# 2_waffling60-NMB_matrix.net
KiCad netlist of a schematic drawn in Altium Designer
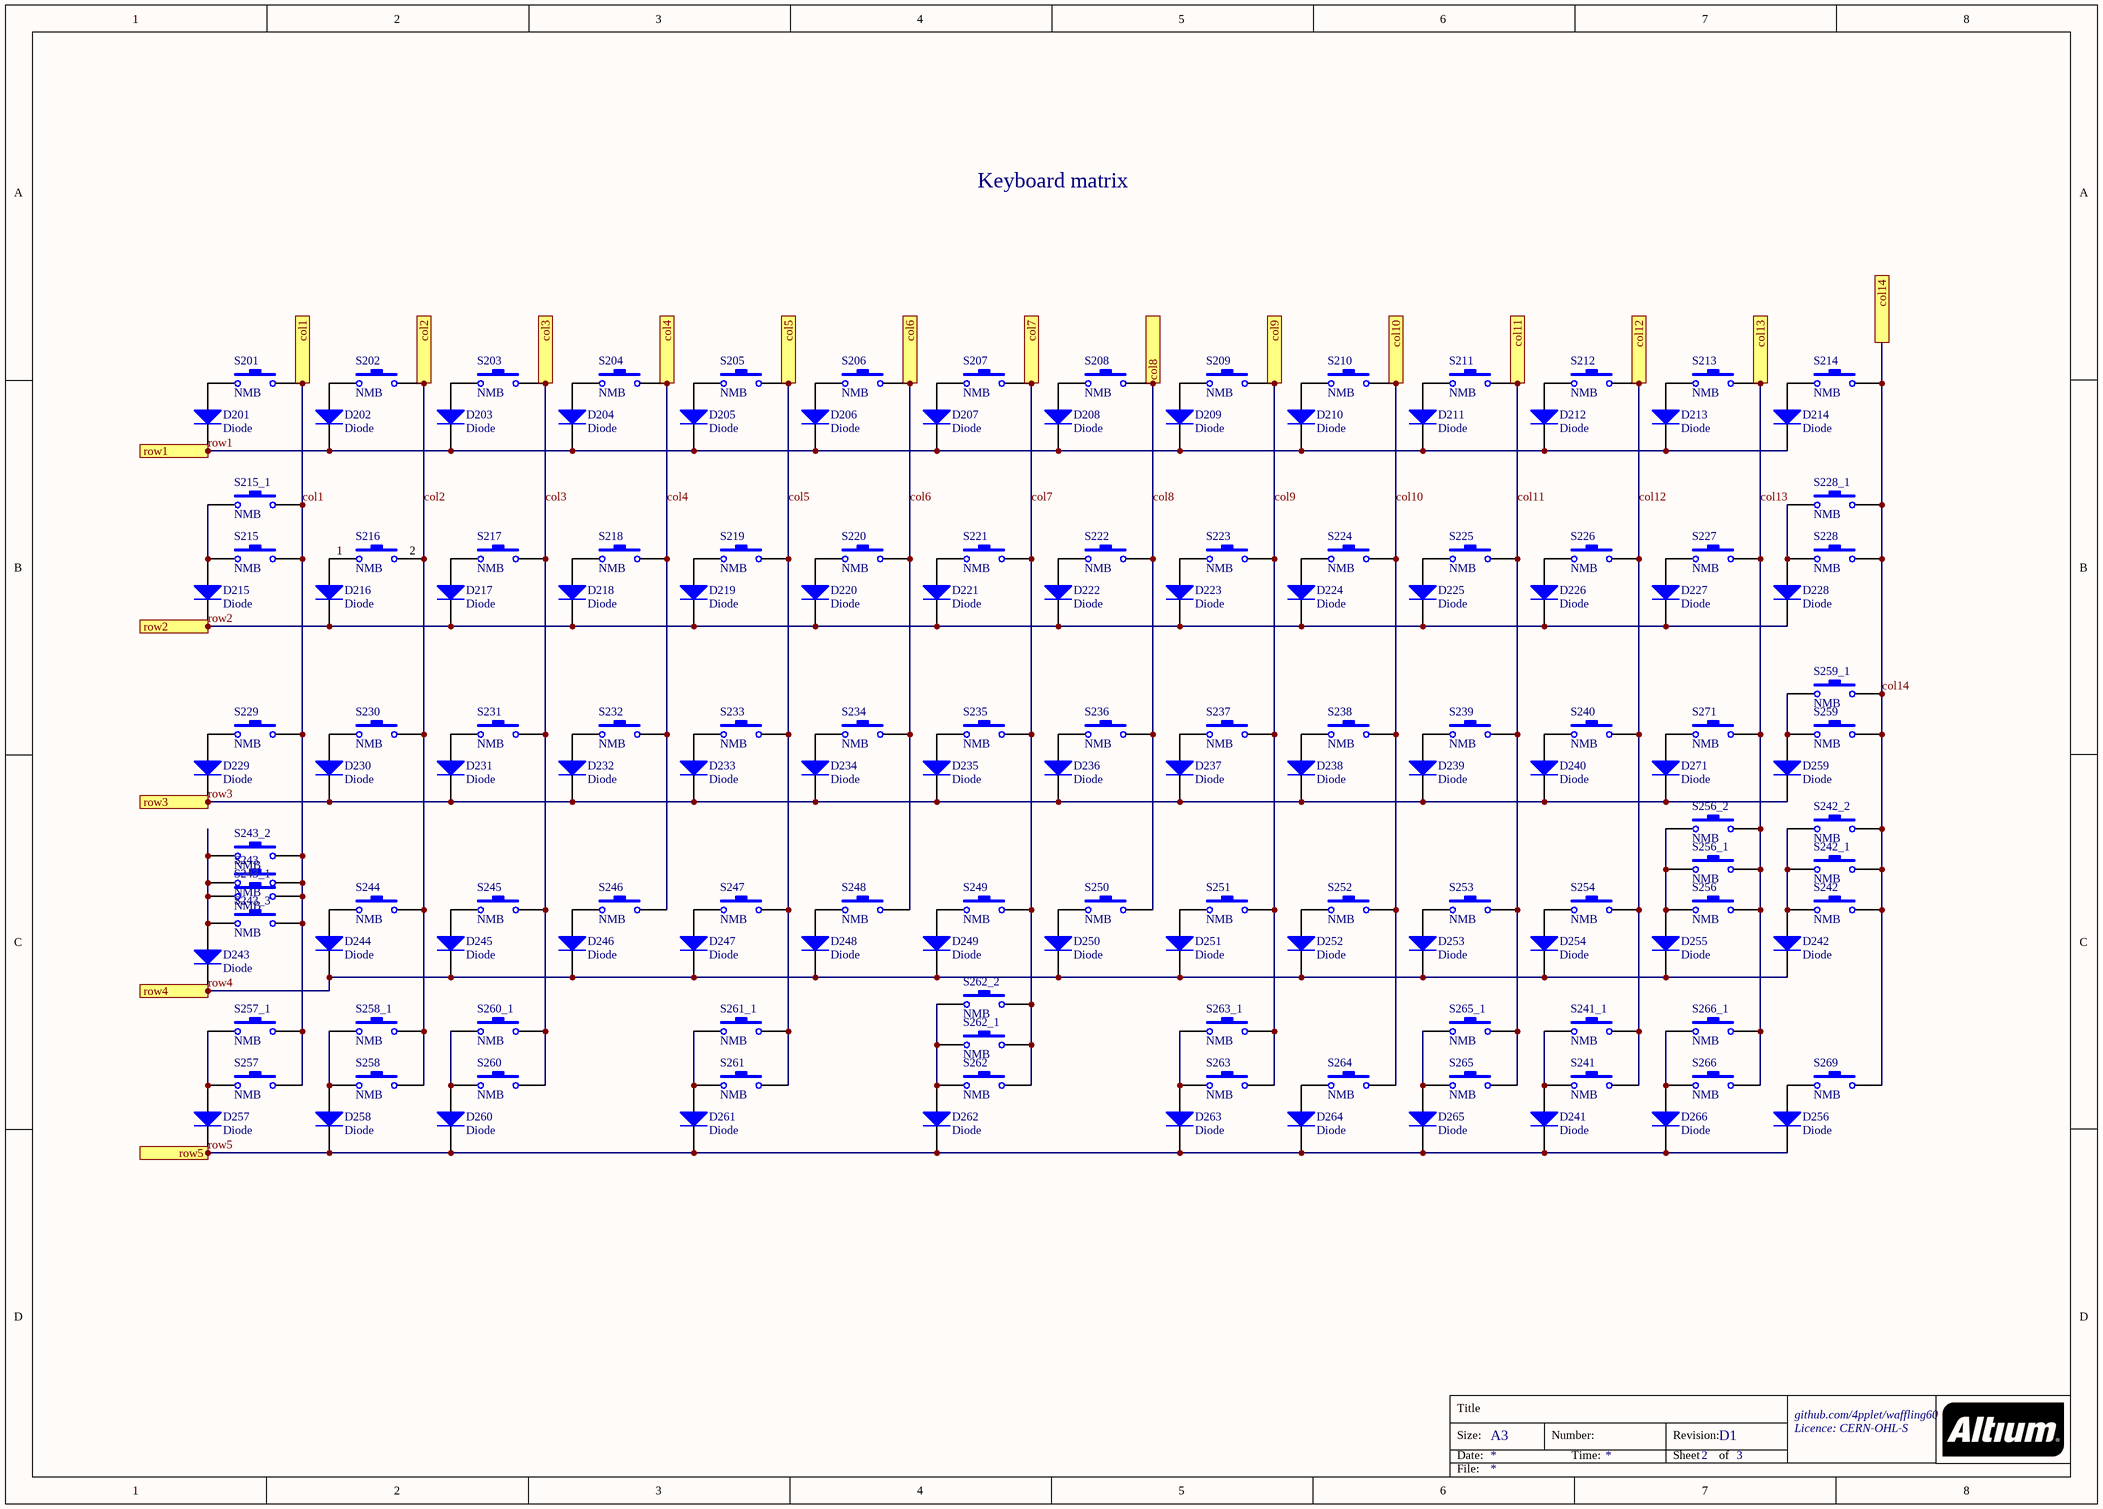
[diagram p0: 2_waffling60-NMB_matrix.SchDoc]

(export (version "E")
  (design (tool "Eeschema 10.0.6"))
  (components
    (comp (ref "D201")
      (value "Diode")
      (footprint "SOD-123")
      (description "Default Diode")
      (fields (field (name "LCSC PART #") "C81598") (field (name "MRF.PART") "1N4148W"))
      (libsource (lib "Miscellaneous Devices") (part "Diode"))
    )
    (comp (ref "D202")
      (value "Diode")
      (footprint "SOD-123")
      (description "Default Diode")
      (fields (field (name "LCSC PART #") "C81598") (field (name "MRF.PART") "1N4148W"))
      (libsource (lib "Miscellaneous Devices") (part "Diode"))
    )
    (comp (ref "D203")
      (value "Diode")
      (footprint "SOD-123")
      (description "Default Diode")
      (fields (field (name "LCSC PART #") "C81598") (field (name "MRF.PART") "1N4148W"))
      (libsource (lib "Miscellaneous Devices") (part "Diode"))
    )
    (comp (ref "D204")
      (value "Diode")
      (footprint "SOD-123")
      (description "Default Diode")
      (fields (field (name "LCSC PART #") "C81598") (field (name "MRF.PART") "1N4148W"))
      (libsource (lib "Miscellaneous Devices") (part "Diode"))
    )
    (comp (ref "D205")
      (value "Diode")
      (footprint "SOD-123")
      (description "Default Diode")
      (fields (field (name "LCSC PART #") "C81598") (field (name "MRF.PART") "1N4148W"))
      (libsource (lib "Miscellaneous Devices") (part "Diode"))
    )
    (comp (ref "D206")
      (value "Diode")
      (footprint "SOD-123")
      (description "Default Diode")
      (fields (field (name "LCSC PART #") "C81598") (field (name "MRF.PART") "1N4148W"))
      (libsource (lib "Miscellaneous Devices") (part "Diode"))
    )
    (comp (ref "D207")
      (value "Diode")
      (footprint "SOD-123")
      (description "Default Diode")
      (fields (field (name "LCSC PART #") "C81598") (field (name "MRF.PART") "1N4148W"))
      (libsource (lib "Miscellaneous Devices") (part "Diode"))
    )
    (comp (ref "D208")
      (value "Diode")
      (footprint "SOD-123")
      (description "Default Diode")
      (fields (field (name "LCSC PART #") "C81598") (field (name "MRF.PART") "1N4148W"))
      (libsource (lib "Miscellaneous Devices") (part "Diode"))
    )
    (comp (ref "D209")
      (value "Diode")
      (footprint "SOD-123")
      (description "Default Diode")
      (fields (field (name "LCSC PART #") "C81598") (field (name "MRF.PART") "1N4148W"))
      (libsource (lib "Miscellaneous Devices") (part "Diode"))
    )
    (comp (ref "D210")
      (value "Diode")
      (footprint "SOD-123")
      (description "Default Diode")
      (fields (field (name "LCSC PART #") "C81598") (field (name "MRF.PART") "1N4148W"))
      (libsource (lib "Miscellaneous Devices") (part "Diode"))
    )
    (comp (ref "D211")
      (value "Diode")
      (footprint "SOD-123")
      (description "Default Diode")
      (fields (field (name "LCSC PART #") "C81598") (field (name "MRF.PART") "1N4148W"))
      (libsource (lib "Miscellaneous Devices") (part "Diode"))
    )
    (comp (ref "D212")
      (value "Diode")
      (footprint "SOD-123")
      (description "Default Diode")
      (fields (field (name "LCSC PART #") "C81598") (field (name "MRF.PART") "1N4148W"))
      (libsource (lib "Miscellaneous Devices") (part "Diode"))
    )
    (comp (ref "D213")
      (value "Diode")
      (footprint "SOD-123")
      (description "Default Diode")
      (fields (field (name "LCSC PART #") "C81598") (field (name "MRF.PART") "1N4148W"))
      (libsource (lib "Miscellaneous Devices") (part "Diode"))
    )
    (comp (ref "D214")
      (value "Diode")
      (footprint "SOD-123")
      (description "Default Diode")
      (fields (field (name "LCSC PART #") "C81598") (field (name "MRF.PART") "1N4148W"))
      (libsource (lib "Miscellaneous Devices") (part "Diode"))
    )
    (comp (ref "D215")
      (value "Diode")
      (footprint "SOD-123")
      (description "Default Diode")
      (fields (field (name "LCSC PART #") "C81598") (field (name "MRF.PART") "1N4148W"))
      (libsource (lib "Miscellaneous Devices") (part "Diode"))
    )
    (comp (ref "D216")
      (value "Diode")
      (footprint "SOD-123")
      (description "Default Diode")
      (fields (field (name "LCSC PART #") "C81598") (field (name "MRF.PART") "1N4148W"))
      (libsource (lib "Miscellaneous Devices") (part "Diode"))
    )
    (comp (ref "D217")
      (value "Diode")
      (footprint "SOD-123")
      (description "Default Diode")
      (fields (field (name "LCSC PART #") "C81598") (field (name "MRF.PART") "1N4148W"))
      (libsource (lib "Miscellaneous Devices") (part "Diode"))
    )
    (comp (ref "D218")
      (value "Diode")
      (footprint "SOD-123")
      (description "Default Diode")
      (fields (field (name "LCSC PART #") "C81598") (field (name "MRF.PART") "1N4148W"))
      (libsource (lib "Miscellaneous Devices") (part "Diode"))
    )
    (comp (ref "D219")
      (value "Diode")
      (footprint "SOD-123")
      (description "Default Diode")
      (fields (field (name "LCSC PART #") "C81598") (field (name "MRF.PART") "1N4148W"))
      (libsource (lib "Miscellaneous Devices") (part "Diode"))
    )
    (comp (ref "D220")
      (value "Diode")
      (footprint "SOD-123")
      (description "Default Diode")
      (fields (field (name "LCSC PART #") "C81598") (field (name "MRF.PART") "1N4148W"))
      (libsource (lib "Miscellaneous Devices") (part "Diode"))
    )
    (comp (ref "D221")
      (value "Diode")
      (footprint "SOD-123")
      (description "Default Diode")
      (fields (field (name "LCSC PART #") "C81598") (field (name "MRF.PART") "1N4148W"))
      (libsource (lib "Miscellaneous Devices") (part "Diode"))
    )
    (comp (ref "D222")
      (value "Diode")
      (footprint "SOD-123")
      (description "Default Diode")
      (fields (field (name "LCSC PART #") "C81598") (field (name "MRF.PART") "1N4148W"))
      (libsource (lib "Miscellaneous Devices") (part "Diode"))
    )
    (comp (ref "D223")
      (value "Diode")
      (footprint "SOD-123")
      (description "Default Diode")
      (fields (field (name "LCSC PART #") "C81598") (field (name "MRF.PART") "1N4148W"))
      (libsource (lib "Miscellaneous Devices") (part "Diode"))
    )
    (comp (ref "D224")
      (value "Diode")
      (footprint "SOD-123")
      (description "Default Diode")
      (fields (field (name "LCSC PART #") "C81598") (field (name "MRF.PART") "1N4148W"))
      (libsource (lib "Miscellaneous Devices") (part "Diode"))
    )
    (comp (ref "D225")
      (value "Diode")
      (footprint "SOD-123")
      (description "Default Diode")
      (fields (field (name "LCSC PART #") "C81598") (field (name "MRF.PART") "1N4148W"))
      (libsource (lib "Miscellaneous Devices") (part "Diode"))
    )
    (comp (ref "D226")
      (value "Diode")
      (footprint "SOD-123")
      (description "Default Diode")
      (fields (field (name "LCSC PART #") "C81598") (field (name "MRF.PART") "1N4148W"))
      (libsource (lib "Miscellaneous Devices") (part "Diode"))
    )
    (comp (ref "D227")
      (value "Diode")
      (footprint "SOD-123")
      (description "Default Diode")
      (fields (field (name "LCSC PART #") "C81598") (field (name "MRF.PART") "1N4148W"))
      (libsource (lib "Miscellaneous Devices") (part "Diode"))
    )
    (comp (ref "D228")
      (value "Diode")
      (footprint "SOD-123")
      (description "Default Diode")
      (fields (field (name "LCSC PART #") "C81598") (field (name "MRF.PART") "1N4148W"))
      (libsource (lib "Miscellaneous Devices") (part "Diode"))
    )
    (comp (ref "D229")
      (value "Diode")
      (footprint "SOD-123")
      (description "Default Diode")
      (fields (field (name "LCSC PART #") "C81598") (field (name "MRF.PART") "1N4148W"))
      (libsource (lib "Miscellaneous Devices") (part "Diode"))
    )
    (comp (ref "D230")
      (value "Diode")
      (footprint "SOD-123")
      (description "Default Diode")
      (fields (field (name "LCSC PART #") "C81598") (field (name "MRF.PART") "1N4148W"))
      (libsource (lib "Miscellaneous Devices") (part "Diode"))
    )
    (comp (ref "D231")
      (value "Diode")
      (footprint "SOD-123")
      (description "Default Diode")
      (fields (field (name "LCSC PART #") "C81598") (field (name "MRF.PART") "1N4148W"))
      (libsource (lib "Miscellaneous Devices") (part "Diode"))
    )
    (comp (ref "D232")
      (value "Diode")
      (footprint "SOD-123")
      (description "Default Diode")
      (fields (field (name "LCSC PART #") "C81598") (field (name "MRF.PART") "1N4148W"))
      (libsource (lib "Miscellaneous Devices") (part "Diode"))
    )
    (comp (ref "D233")
      (value "Diode")
      (footprint "SOD-123")
      (description "Default Diode")
      (fields (field (name "LCSC PART #") "C81598") (field (name "MRF.PART") "1N4148W"))
      (libsource (lib "Miscellaneous Devices") (part "Diode"))
    )
    (comp (ref "D234")
      (value "Diode")
      (footprint "SOD-123")
      (description "Default Diode")
      (fields (field (name "LCSC PART #") "C81598") (field (name "MRF.PART") "1N4148W"))
      (libsource (lib "Miscellaneous Devices") (part "Diode"))
    )
    (comp (ref "D235")
      (value "Diode")
      (footprint "SOD-123")
      (description "Default Diode")
      (fields (field (name "LCSC PART #") "C81598") (field (name "MRF.PART") "1N4148W"))
      (libsource (lib "Miscellaneous Devices") (part "Diode"))
    )
    (comp (ref "D236")
      (value "Diode")
      (footprint "SOD-123")
      (description "Default Diode")
      (fields (field (name "LCSC PART #") "C81598") (field (name "MRF.PART") "1N4148W"))
      (libsource (lib "Miscellaneous Devices") (part "Diode"))
    )
    (comp (ref "D237")
      (value "Diode")
      (footprint "SOD-123")
      (description "Default Diode")
      (fields (field (name "LCSC PART #") "C81598") (field (name "MRF.PART") "1N4148W"))
      (libsource (lib "Miscellaneous Devices") (part "Diode"))
    )
    (comp (ref "D238")
      (value "Diode")
      (footprint "SOD-123")
      (description "Default Diode")
      (fields (field (name "LCSC PART #") "C81598") (field (name "MRF.PART") "1N4148W"))
      (libsource (lib "Miscellaneous Devices") (part "Diode"))
    )
    (comp (ref "D239")
      (value "Diode")
      (footprint "SOD-123")
      (description "Default Diode")
      (fields (field (name "LCSC PART #") "C81598") (field (name "MRF.PART") "1N4148W"))
      (libsource (lib "Miscellaneous Devices") (part "Diode"))
    )
    (comp (ref "D240")
      (value "Diode")
      (footprint "SOD-123")
      (description "Default Diode")
      (fields (field (name "LCSC PART #") "C81598") (field (name "MRF.PART") "1N4148W"))
      (libsource (lib "Miscellaneous Devices") (part "Diode"))
    )
    (comp (ref "D241")
      (value "Diode")
      (footprint "SOD-123")
      (description "Default Diode")
      (fields (field (name "LCSC PART #") "C81598") (field (name "MRF.PART") "1N4148W"))
      (libsource (lib "Miscellaneous Devices") (part "Diode"))
    )
    (comp (ref "D242")
      (value "Diode")
      (footprint "SOD-123")
      (description "Default Diode")
      (fields (field (name "LCSC PART #") "C81598") (field (name "MRF.PART") "1N4148W"))
      (libsource (lib "Miscellaneous Devices") (part "Diode"))
    )
    (comp (ref "D243")
      (value "Diode")
      (footprint "SOD-123")
      (description "Default Diode")
      (fields (field (name "LCSC PART #") "C81598") (field (name "MRF.PART") "1N4148W"))
      (libsource (lib "Miscellaneous Devices") (part "Diode"))
    )
    (comp (ref "D244")
      (value "Diode")
      (footprint "SOD-123")
      (description "Default Diode")
      (fields (field (name "LCSC PART #") "C81598") (field (name "MRF.PART") "1N4148W"))
      (libsource (lib "Miscellaneous Devices") (part "Diode"))
    )
    (comp (ref "D245")
      (value "Diode")
      (footprint "SOD-123")
      (description "Default Diode")
      (fields (field (name "LCSC PART #") "C81598") (field (name "MRF.PART") "1N4148W"))
      (libsource (lib "Miscellaneous Devices") (part "Diode"))
    )
    (comp (ref "D246")
      (value "Diode")
      (footprint "SOD-123")
      (description "Default Diode")
      (fields (field (name "LCSC PART #") "C81598") (field (name "MRF.PART") "1N4148W"))
      (libsource (lib "Miscellaneous Devices") (part "Diode"))
    )
    (comp (ref "D247")
      (value "Diode")
      (footprint "SOD-123")
      (description "Default Diode")
      (fields (field (name "LCSC PART #") "C81598") (field (name "MRF.PART") "1N4148W"))
      (libsource (lib "Miscellaneous Devices") (part "Diode"))
    )
    (comp (ref "D248")
      (value "Diode")
      (footprint "SOD-123")
      (description "Default Diode")
      (fields (field (name "LCSC PART #") "C81598") (field (name "MRF.PART") "1N4148W"))
      (libsource (lib "Miscellaneous Devices") (part "Diode"))
    )
    (comp (ref "D249")
      (value "Diode")
      (footprint "SOD-123")
      (description "Default Diode")
      (fields (field (name "LCSC PART #") "C81598") (field (name "MRF.PART") "1N4148W"))
      (libsource (lib "Miscellaneous Devices") (part "Diode"))
    )
    (comp (ref "D250")
      (value "Diode")
      (footprint "SOD-123")
      (description "Default Diode")
      (fields (field (name "LCSC PART #") "C81598") (field (name "MRF.PART") "1N4148W"))
      (libsource (lib "Miscellaneous Devices") (part "Diode"))
    )
    (comp (ref "D251")
      (value "Diode")
      (footprint "SOD-123")
      (description "Default Diode")
      (fields (field (name "LCSC PART #") "C81598") (field (name "MRF.PART") "1N4148W"))
      (libsource (lib "Miscellaneous Devices") (part "Diode"))
    )
    (comp (ref "D252")
      (value "Diode")
      (footprint "SOD-123")
      (description "Default Diode")
      (fields (field (name "LCSC PART #") "C81598") (field (name "MRF.PART") "1N4148W"))
      (libsource (lib "Miscellaneous Devices") (part "Diode"))
    )
    (comp (ref "D253")
      (value "Diode")
      (footprint "SOD-123")
      (description "Default Diode")
      (fields (field (name "LCSC PART #") "C81598") (field (name "MRF.PART") "1N4148W"))
      (libsource (lib "Miscellaneous Devices") (part "Diode"))
    )
    (comp (ref "D254")
      (value "Diode")
      (footprint "SOD-123")
      (description "Default Diode")
      (fields (field (name "LCSC PART #") "C81598") (field (name "MRF.PART") "1N4148W"))
      (libsource (lib "Miscellaneous Devices") (part "Diode"))
    )
    (comp (ref "D255")
      (value "Diode")
      (footprint "SOD-123")
      (description "Default Diode")
      (fields (field (name "LCSC PART #") "C81598") (field (name "MRF.PART") "1N4148W"))
      (libsource (lib "Miscellaneous Devices") (part "Diode"))
    )
    (comp (ref "D256")
      (value "Diode")
      (footprint "SOD-123")
      (description "Default Diode")
      (fields (field (name "LCSC PART #") "C81598") (field (name "MRF.PART") "1N4148W"))
      (libsource (lib "Miscellaneous Devices") (part "Diode"))
    )
    (comp (ref "D257")
      (value "Diode")
      (footprint "SOD-123")
      (description "Default Diode")
      (fields (field (name "LCSC PART #") "C81598") (field (name "MRF.PART") "1N4148W"))
      (libsource (lib "Miscellaneous Devices") (part "Diode"))
    )
    (comp (ref "D258")
      (value "Diode")
      (footprint "SOD-123")
      (description "Default Diode")
      (fields (field (name "LCSC PART #") "C81598") (field (name "MRF.PART") "1N4148W"))
      (libsource (lib "Miscellaneous Devices") (part "Diode"))
    )
    (comp (ref "D259")
      (value "Diode")
      (footprint "SOD-123")
      (description "Default Diode")
      (fields (field (name "LCSC PART #") "C81598") (field (name "MRF.PART") "1N4148W"))
      (libsource (lib "Miscellaneous Devices") (part "Diode"))
    )
    (comp (ref "D260")
      (value "Diode")
      (footprint "SOD-123")
      (description "Default Diode")
      (fields (field (name "LCSC PART #") "C81598") (field (name "MRF.PART") "1N4148W"))
      (libsource (lib "Miscellaneous Devices") (part "Diode"))
    )
    (comp (ref "D261")
      (value "Diode")
      (footprint "SOD-123")
      (description "Default Diode")
      (fields (field (name "LCSC PART #") "C81598") (field (name "MRF.PART") "1N4148W"))
      (libsource (lib "Miscellaneous Devices") (part "Diode"))
    )
    (comp (ref "D262")
      (value "Diode")
      (footprint "SOD-123")
      (description "Default Diode")
      (fields (field (name "LCSC PART #") "C81598") (field (name "MRF.PART") "1N4148W"))
      (libsource (lib "Miscellaneous Devices") (part "Diode"))
    )
    (comp (ref "D263")
      (value "Diode")
      (footprint "SOD-123")
      (description "Default Diode")
      (fields (field (name "LCSC PART #") "C81598") (field (name "MRF.PART") "1N4148W"))
      (libsource (lib "Miscellaneous Devices") (part "Diode"))
    )
    (comp (ref "D264")
      (value "Diode")
      (footprint "SOD-123")
      (description "Default Diode")
      (fields (field (name "LCSC PART #") "C81598") (field (name "MRF.PART") "1N4148W"))
      (libsource (lib "Miscellaneous Devices") (part "Diode"))
    )
    (comp (ref "D265")
      (value "Diode")
      (footprint "SOD-123")
      (description "Default Diode")
      (fields (field (name "LCSC PART #") "C81598") (field (name "MRF.PART") "1N4148W"))
      (libsource (lib "Miscellaneous Devices") (part "Diode"))
    )
    (comp (ref "D266")
      (value "Diode")
      (footprint "SOD-123")
      (description "Default Diode")
      (fields (field (name "LCSC PART #") "C81598") (field (name "MRF.PART") "1N4148W"))
      (libsource (lib "Miscellaneous Devices") (part "Diode"))
    )
    (comp (ref "D271")
      (value "Diode")
      (footprint "SOD-123")
      (description "Default Diode")
      (fields (field (name "LCSC PART #") "C81598") (field (name "MRF.PART") "1N4148W"))
      (libsource (lib "Miscellaneous Devices") (part "Diode"))
    )
    (comp (ref "S201")
      (value "NMB")
      (footprint "NMB-Switch 1U - switched pol  - no allignment pins")
      (description "Switch")
      (libsource (lib "Miscellaneous Devices") (part "SW-PB"))
    )
    (comp (ref "S202")
      (value "NMB")
      (footprint "NMB-Switch 1U - no allignment pins")
      (description "Switch")
      (libsource (lib "Miscellaneous Devices") (part "SW-PB"))
    )
    (comp (ref "S203")
      (value "NMB")
      (footprint "NMB-Switch 1U - switched pol  - no allignment pins")
      (description "Switch")
      (libsource (lib "Miscellaneous Devices") (part "SW-PB"))
    )
    (comp (ref "S204")
      (value "NMB")
      (footprint "NMB-Switch 1U - switched pol  - no allignment pins")
      (description "Switch")
      (libsource (lib "Miscellaneous Devices") (part "SW-PB"))
    )
    (comp (ref "S205")
      (value "NMB")
      (footprint "NMB-Switch 1U - switched pol  - no allignment pins")
      (description "Switch")
      (libsource (lib "Miscellaneous Devices") (part "SW-PB"))
    )
    (comp (ref "S206")
      (value "NMB")
      (footprint "NMB-Switch 1U - switched pol  - no allignment pins")
      (description "Switch")
      (libsource (lib "Miscellaneous Devices") (part "SW-PB"))
    )
    (comp (ref "S207")
      (value "NMB")
      (footprint "NMB-Switch 1U - switched pol  - no allignment pins")
      (description "Switch")
      (libsource (lib "Miscellaneous Devices") (part "SW-PB"))
    )
    (comp (ref "S208")
      (value "NMB")
      (footprint "NMB-Switch 1U - switched pol  - no allignment pins")
      (description "Switch")
      (libsource (lib "Miscellaneous Devices") (part "SW-PB"))
    )
    (comp (ref "S209")
      (value "NMB")
      (footprint "NMB-Switch 1U - switched pol  - no allignment pins")
      (description "Switch")
      (libsource (lib "Miscellaneous Devices") (part "SW-PB"))
    )
    (comp (ref "S210")
      (value "NMB")
      (footprint "NMB-Switch 1U - switched pol  - no allignment pins")
      (description "Switch")
      (libsource (lib "Miscellaneous Devices") (part "SW-PB"))
    )
    (comp (ref "S211")
      (value "NMB")
      (footprint "NMB-Switch 1U - switched pol  - no allignment pins")
      (description "Switch")
      (libsource (lib "Miscellaneous Devices") (part "SW-PB"))
    )
    (comp (ref "S212")
      (value "NMB")
      (footprint "NMB-Switch 1U - switched pol  - no allignment pins")
      (description "Switch")
      (libsource (lib "Miscellaneous Devices") (part "SW-PB"))
    )
    (comp (ref "S213")
      (value "NMB")
      (footprint "NMB-Switch 1U - switched pol  - no allignment pins")
      (description "Switch")
      (libsource (lib "Miscellaneous Devices") (part "SW-PB"))
    )
    (comp (ref "S214")
      (value "NMB")
      (footprint "NMB-Switch 1U - no allignment pins")
      (description "Switch")
      (libsource (lib "Miscellaneous Devices") (part "SW-PB"))
    )
    (comp (ref "S215")
      (value "NMB")
      (footprint "NMB-Switch 1U - no allignment pins")
      (description "TAB")
      (libsource (lib "Miscellaneous Devices") (part "SW-PB"))
    )
    (comp (ref "S215_1")
      (value "NMB")
      (footprint "NMB-Switch 1U - no allignment pins")
      (description "TAB")
      (libsource (lib "Miscellaneous Devices") (part "SW-PB"))
    )
    (comp (ref "S216")
      (value "NMB")
      (footprint "NMB-Switch 1U - switched pol  - no allignment pins")
      (description "Switch")
      (libsource (lib "") (part "SW-PB_2"))
    )
    (comp (ref "S217")
      (value "NMB")
      (footprint "NMB-Switch 1U - switched pol  - no allignment pins")
      (description "Switch")
      (libsource (lib "Miscellaneous Devices") (part "SW-PB"))
    )
    (comp (ref "S218")
      (value "NMB")
      (footprint "NMB-Switch 1U - switched pol  - no allignment pins")
      (description "Switch")
      (libsource (lib "Miscellaneous Devices") (part "SW-PB"))
    )
    (comp (ref "S219")
      (value "NMB")
      (footprint "NMB-Switch 1U - switched pol  - no allignment pins")
      (description "Switch")
      (libsource (lib "Miscellaneous Devices") (part "SW-PB"))
    )
    (comp (ref "S220")
      (value "NMB")
      (footprint "NMB-Switch 1U - no allignment pins")
      (description "Switch")
      (libsource (lib "Miscellaneous Devices") (part "SW-PB"))
    )
    (comp (ref "S221")
      (value "NMB")
      (footprint "NMB-Switch 1U - switched pol  - no allignment pins")
      (description "Switch")
      (libsource (lib "Miscellaneous Devices") (part "SW-PB"))
    )
    (comp (ref "S222")
      (value "NMB")
      (footprint "NMB-Switch 1U - no allignment pins")
      (description "Switch")
      (libsource (lib "Miscellaneous Devices") (part "SW-PB"))
    )
    (comp (ref "S223")
      (value "NMB")
      (footprint "NMB-Switch 1U - switched pol  - no allignment pins")
      (description "Switch")
      (libsource (lib "Miscellaneous Devices") (part "SW-PB"))
    )
    (comp (ref "S224")
      (value "NMB")
      (footprint "NMB-Switch 1U - switched pol  - no allignment pins")
      (description "Switch")
      (libsource (lib "Miscellaneous Devices") (part "SW-PB"))
    )
    (comp (ref "S225")
      (value "NMB")
      (footprint "NMB-Switch 1U - switched pol  - no allignment pins")
      (description "Switch")
      (libsource (lib "Miscellaneous Devices") (part "SW-PB"))
    )
    (comp (ref "S226")
      (value "NMB")
      (footprint "NMB-Switch 1U - no allignment pins")
      (description "Switch")
      (libsource (lib "Miscellaneous Devices") (part "SW-PB"))
    )
    (comp (ref "S227")
      (value "NMB")
      (footprint "NMB-Switch 1U - no allignment pins")
      (description "Switch")
      (libsource (lib "Miscellaneous Devices") (part "SW-PB"))
    )
    (comp (ref "S228")
      (value "NMB")
      (footprint "NMB-Switch 1U - no allignment pins")
      (description "Switch")
      (libsource (lib "Miscellaneous Devices") (part "SW-PB"))
    )
    (comp (ref "S228_1")
      (value "NMB")
      (footprint "NMB-Switch 1U - no allignment pins")
      (description "Switch")
      (libsource (lib "Miscellaneous Devices") (part "SW-PB"))
    )
    (comp (ref "S229")
      (value "NMB")
      (footprint "NMB-Switch 1U - no allignment pins")
      (description "Switch")
      (libsource (lib "Miscellaneous Devices") (part "SW-PB"))
    )
    (comp (ref "S230")
      (value "NMB")
      (footprint "NMB-Switch 1U - no allignment pins")
      (description "Switch")
      (libsource (lib "Miscellaneous Devices") (part "SW-PB"))
    )
    (comp (ref "S231")
      (value "NMB")
      (footprint "NMB-Switch 1U - switched pol  - no allignment pins")
      (description "Switch")
      (libsource (lib "Miscellaneous Devices") (part "SW-PB"))
    )
    (comp (ref "S232")
      (value "NMB")
      (footprint "NMB-Switch 1U - switched pol  - no allignment pins")
      (description "Switch")
      (libsource (lib "Miscellaneous Devices") (part "SW-PB"))
    )
    (comp (ref "S233")
      (value "NMB")
      (footprint "NMB-Switch 1U - switched pol  - no allignment pins")
      (description "Switch")
      (libsource (lib "Miscellaneous Devices") (part "SW-PB"))
    )
    (comp (ref "S234")
      (value "NMB")
      (footprint "NMB-Switch 1U - no allignment pins")
      (description "Switch")
      (libsource (lib "Miscellaneous Devices") (part "SW-PB"))
    )
    (comp (ref "S235")
      (value "NMB")
      (footprint "NMB-Switch 1U - switched pol  - no allignment pins")
      (description "Switch")
      (libsource (lib "Miscellaneous Devices") (part "SW-PB"))
    )
    (comp (ref "S236")
      (value "NMB")
      (footprint "NMB-Switch 1U - switched pol  - no allignment pins")
      (description "Switch")
      (libsource (lib "Miscellaneous Devices") (part "SW-PB"))
    )
    (comp (ref "S237")
      (value "NMB")
      (footprint "NMB-Switch 1U - switched pol  - no allignment pins")
      (description "Switch")
      (libsource (lib "Miscellaneous Devices") (part "SW-PB"))
    )
    (comp (ref "S238")
      (value "NMB")
      (footprint "NMB-Switch 1U - switched pol  - no allignment pins")
      (description "Switch")
      (libsource (lib "Miscellaneous Devices") (part "SW-PB"))
    )
    (comp (ref "S239")
      (value "NMB")
      (footprint "NMB-Switch 1U - switched pol  - no allignment pins")
      (description "Switch")
      (libsource (lib "Miscellaneous Devices") (part "SW-PB"))
    )
    (comp (ref "S240")
      (value "NMB")
      (footprint "NMB-Switch 1U - switched pol  - no allignment pins")
      (description "Switch")
      (libsource (lib "Miscellaneous Devices") (part "SW-PB"))
    )
    (comp (ref "S241")
      (value "NMB")
      (footprint "NMB-Switch 1U - no allignment pins")
      (description "Switch")
      (libsource (lib "Miscellaneous Devices") (part "SW-PB"))
    )
    (comp (ref "S241_1")
      (value "NMB")
      (footprint "NMB-Switch 1U - no allignment pins")
      (description "Switch")
      (libsource (lib "Miscellaneous Devices") (part "SW-PB"))
    )
    (comp (ref "S242")
      (value "NMB")
      (footprint "NMB-Switch 1U - switched pol  - no allignment pins")
      (description "Switch")
      (libsource (lib "Miscellaneous Devices") (part "SW-PB"))
    )
    (comp (ref "S242_1")
      (value "NMB")
      (footprint "NMB-Switch 1U - no allignment pins")
      (description "Switch")
      (libsource (lib "Miscellaneous Devices") (part "SW-PB"))
    )
    (comp (ref "S242_2")
      (value "NMB")
      (footprint "NMB-Switch 1U - switched pol  - no allignment pins")
      (description "Switch")
      (libsource (lib "Miscellaneous Devices") (part "SW-PB"))
    )
    (comp (ref "S243")
      (value "NMB")
      (footprint "NMB-Switch 1U - switched pol  - no allignment pins")
      (description "Switch")
      (libsource (lib "Miscellaneous Devices") (part "SW-PB"))
    )
    (comp (ref "S243_1")
      (value "NMB")
      (footprint "NMB-Switch 1U - switched pol  - no allignment pins")
      (description "Switch")
      (libsource (lib "Miscellaneous Devices") (part "SW-PB"))
    )
    (comp (ref "S243_2")
      (value "NMB")
      (footprint "NMB-Switch 1U - no allignment pins")
      (description "Switch")
      (libsource (lib "Miscellaneous Devices") (part "SW-PB"))
    )
    (comp (ref "S243_3")
      (value "NMB")
      (footprint "NMB-Switch 1U - no allignment pins")
      (description "Switch")
      (libsource (lib "Miscellaneous Devices") (part "SW-PB"))
    )
    (comp (ref "S244")
      (value "NMB")
      (footprint "NMB-Switch 1U - no allignment pins")
      (description "Switch")
      (libsource (lib "Miscellaneous Devices") (part "SW-PB"))
    )
    (comp (ref "S245")
      (value "NMB")
      (footprint "NMB-Switch 1U - switched pol  - no allignment pins")
      (description "Switch")
      (libsource (lib "Miscellaneous Devices") (part "SW-PB"))
    )
    (comp (ref "S246")
      (value "NMB")
      (footprint "NMB-Switch 1U - switched pol  - no allignment pins")
      (description "Switch")
      (libsource (lib "Miscellaneous Devices") (part "SW-PB"))
    )
    (comp (ref "S247")
      (value "NMB")
      (footprint "NMB-Switch 1U - switched pol  - no allignment pins")
      (description "Switch")
      (libsource (lib "Miscellaneous Devices") (part "SW-PB"))
    )
    (comp (ref "S248")
      (value "NMB")
      (footprint "NMB-Switch 1U - switched pol  - no allignment pins")
      (description "Switch")
      (libsource (lib "Miscellaneous Devices") (part "SW-PB"))
    )
    (comp (ref "S249")
      (value "NMB")
      (footprint "NMB-Switch 1U - switched pol  - no allignment pins")
      (description "Switch")
      (libsource (lib "Miscellaneous Devices") (part "SW-PB"))
    )
    (comp (ref "S250")
      (value "NMB")
      (footprint "NMB-Switch 1U - switched pol  - no allignment pins")
      (description "Switch")
      (libsource (lib "Miscellaneous Devices") (part "SW-PB"))
    )
    (comp (ref "S251")
      (value "NMB")
      (footprint "NMB-Switch 1U - switched pol  - no allignment pins")
      (description "Switch")
      (libsource (lib "Miscellaneous Devices") (part "SW-PB"))
    )
    (comp (ref "S252")
      (value "NMB")
      (footprint "NMB-Switch 1U - switched pol  - no allignment pins")
      (description "Switch")
      (libsource (lib "Miscellaneous Devices") (part "SW-PB"))
    )
    (comp (ref "S253")
      (value "NMB")
      (footprint "NMB-Switch 1U - switched pol  - no allignment pins")
      (description "Switch")
      (libsource (lib "Miscellaneous Devices") (part "SW-PB"))
    )
    (comp (ref "S254")
      (value "NMB")
      (footprint "NMB-Switch 1U - switched pol  - no allignment pins")
      (description "Switch")
      (libsource (lib "Miscellaneous Devices") (part "SW-PB"))
    )
    (comp (ref "S256")
      (value "NMB")
      (footprint "NMB-Switch 1U - switched pol  - no allignment pins")
      (description "Switch")
      (libsource (lib "Miscellaneous Devices") (part "SW-PB"))
    )
    (comp (ref "S256_1")
      (value "NMB")
      (footprint "NMB-Switch 1U - switched pol  - no allignment pins")
      (description "Switch")
      (libsource (lib "Miscellaneous Devices") (part "SW-PB"))
    )
    (comp (ref "S256_2")
      (value "NMB")
      (footprint "NMB-Switch 1U - no allignment pins")
      (description "Switch")
      (libsource (lib "Miscellaneous Devices") (part "SW-PB"))
    )
    (comp (ref "S257")
      (value "NMB")
      (footprint "NMB-Switch 1U - no allignment pins")
      (description "Switch")
      (libsource (lib "Miscellaneous Devices") (part "SW-PB"))
    )
    (comp (ref "S257_1")
      (value "NMB")
      (footprint "NMB-Switch 1U - no allignment pins")
      (description "Switch")
      (libsource (lib "Miscellaneous Devices") (part "SW-PB"))
    )
    (comp (ref "S258")
      (value "NMB")
      (footprint "NMB-Switch 1U - no allignment pins")
      (description "Switch")
      (libsource (lib "Miscellaneous Devices") (part "SW-PB"))
    )
    (comp (ref "S258_1")
      (value "NMB")
      (footprint "NMB-Switch 1U - switched pol  - no allignment pins")
      (description "Switch")
      (libsource (lib "Miscellaneous Devices") (part "SW-PB"))
    )
    (comp (ref "S259")
      (value "NMB")
      (footprint "NMB-Switch 1U - no allignment pins")
      (description "Switch")
      (libsource (lib "") (part "SW-PB_1"))
    )
    (comp (ref "S259_1")
      (value "NMB")
      (footprint "NMB-Switch 1U - no allignment pins")
      (description "Switch")
      (libsource (lib "Miscellaneous Devices") (part "SW-PB"))
    )
    (comp (ref "S260")
      (value "NMB")
      (footprint "NMB-Switch 1U - no allignment pins")
      (description "Switch")
      (libsource (lib "Miscellaneous Devices") (part "SW-PB"))
    )
    (comp (ref "S260_1")
      (value "NMB")
      (footprint "NMB-Switch 1U - switched pol  - no allignment pins")
      (description "Switch")
      (libsource (lib "Miscellaneous Devices") (part "SW-PB"))
    )
    (comp (ref "S261")
      (value "NMB")
      (footprint "NMB-Switch 1U - no allignment pins")
      (description "Switch")
      (libsource (lib "Miscellaneous Devices") (part "SW-PB"))
    )
    (comp (ref "S261_1")
      (value "NMB")
      (footprint "NMB-Switch 1U - no allignment pins")
      (description "Switch")
      (libsource (lib "Miscellaneous Devices") (part "SW-PB"))
    )
    (comp (ref "S262")
      (value "NMB")
      (footprint "NMB-Switch 1U - no allignment pins")
      (description "Switch")
      (libsource (lib "Miscellaneous Devices") (part "SW-PB"))
    )
    (comp (ref "S262_1")
      (value "NMB")
      (footprint "NMB-Switch 1U - no allignment pins")
      (description "Switch")
      (libsource (lib "Miscellaneous Devices") (part "SW-PB"))
    )
    (comp (ref "S262_2")
      (value "NMB")
      (footprint "NMB-Switch 1U - switched pol  - no allignment pins")
      (description "Switch")
      (libsource (lib "Miscellaneous Devices") (part "SW-PB"))
    )
    (comp (ref "S263")
      (value "NMB")
      (footprint "NMB-Switch 1U - no allignment pins")
      (description "Switch")
      (libsource (lib "Miscellaneous Devices") (part "SW-PB"))
    )
    (comp (ref "S263_1")
      (value "NMB")
      (footprint "NMB-Switch 1U - switched pol  - no allignment pins")
      (description "Switch")
      (libsource (lib "Miscellaneous Devices") (part "SW-PB"))
    )
    (comp (ref "S264")
      (value "NMB")
      (footprint "NMB-Switch 1U - switched pol  - no allignment pins")
      (description "Switch")
      (libsource (lib "Miscellaneous Devices") (part "SW-PB"))
    )
    (comp (ref "S265")
      (value "NMB")
      (footprint "NMB-Switch 1U - no allignment pins")
      (description "Switch")
      (libsource (lib "Miscellaneous Devices") (part "SW-PB"))
    )
    (comp (ref "S265_1")
      (value "NMB")
      (footprint "NMB-Switch 1U - no allignment pins")
      (description "Switch")
      (libsource (lib "Miscellaneous Devices") (part "SW-PB"))
    )
    (comp (ref "S266")
      (value "NMB")
      (footprint "NMB-Switch 1U - no allignment pins")
      (description "Switch")
      (libsource (lib "Miscellaneous Devices") (part "SW-PB"))
    )
    (comp (ref "S266_1")
      (value "NMB")
      (footprint "NMB-Switch 1U - no allignment pins")
      (description "Switch")
      (libsource (lib "Miscellaneous Devices") (part "SW-PB"))
    )
    (comp (ref "S269")
      (value "NMB")
      (footprint "NMB-Switch 1U - no allignment pins")
      (description "Switch")
      (libsource (lib "Miscellaneous Devices") (part "SW-PB"))
    )
    (comp (ref "S271")
      (value "NMB")
      (footprint "NMB-Switch 1U - no allignment pins")
      (description "Switch")
      (libsource (lib "Miscellaneous Devices") (part "SW-PB"))
    )
  )
  (nets
    (net (code "1") (name "/col1") (class "Default")
      (node (ref "S201") (pin "2") (pinfunction "2_2") (pintype "passive"))
      (node (ref "S215") (pin "2") (pinfunction "2_2") (pintype "passive"))
      (node (ref "S215_1") (pin "2") (pinfunction "2_2") (pintype "passive"))
      (node (ref "S229") (pin "1") (pinfunction "1_1") (pintype "passive"))
      (node (ref "S243") (pin "2") (pinfunction "2_2") (pintype "passive"))
      (node (ref "S243_1") (pin "2") (pinfunction "2_2") (pintype "passive"))
      (node (ref "S243_2") (pin "2") (pinfunction "2_2") (pintype "passive"))
      (node (ref "S243_3") (pin "2") (pinfunction "2_2") (pintype "passive"))
      (node (ref "S257") (pin "1") (pinfunction "1_1") (pintype "passive"))
      (node (ref "S257_1") (pin "1") (pinfunction "1_1") (pintype "passive"))
    )
    (net (code "2") (name "/col2") (class "Default")
      (node (ref "S202") (pin "2") (pinfunction "2_2") (pintype "passive"))
      (node (ref "S216") (pin "2") (pinfunction "2_2") (pintype "passive"))
      (node (ref "S230") (pin "2") (pinfunction "2_2") (pintype "passive"))
      (node (ref "S244") (pin "1") (pinfunction "1_1") (pintype "passive"))
      (node (ref "S258") (pin "2") (pinfunction "2_2") (pintype "passive"))
      (node (ref "S258_1") (pin "1") (pinfunction "1_1") (pintype "passive"))
    )
    (net (code "3") (name "/col3") (class "Default")
      (node (ref "S203") (pin "2") (pinfunction "2_2") (pintype "passive"))
      (node (ref "S217") (pin "2") (pinfunction "2_2") (pintype "passive"))
      (node (ref "S231") (pin "2") (pinfunction "2_2") (pintype "passive"))
      (node (ref "S245") (pin "2") (pinfunction "2_2") (pintype "passive"))
      (node (ref "S260") (pin "2") (pinfunction "2_2") (pintype "passive"))
      (node (ref "S260_1") (pin "1") (pinfunction "1_1") (pintype "passive"))
    )
    (net (code "4") (name "/col4") (class "Default")
      (node (ref "S204") (pin "2") (pinfunction "2_2") (pintype "passive"))
      (node (ref "S218") (pin "2") (pinfunction "2_2") (pintype "passive"))
      (node (ref "S232") (pin "2") (pinfunction "2_2") (pintype "passive"))
      (node (ref "S246") (pin "2") (pinfunction "2_2") (pintype "passive"))
    )
    (net (code "5") (name "/col5") (class "Default")
      (node (ref "S205") (pin "2") (pinfunction "2_2") (pintype "passive"))
      (node (ref "S219") (pin "2") (pinfunction "2_2") (pintype "passive"))
      (node (ref "S233") (pin "2") (pinfunction "2_2") (pintype "passive"))
      (node (ref "S247") (pin "2") (pinfunction "2_2") (pintype "passive"))
      (node (ref "S261") (pin "2") (pinfunction "2_2") (pintype "passive"))
      (node (ref "S261_1") (pin "2") (pinfunction "2_2") (pintype "passive"))
    )
    (net (code "6") (name "/col6") (class "Default")
      (node (ref "S206") (pin "2") (pinfunction "2_2") (pintype "passive"))
      (node (ref "S220") (pin "2") (pinfunction "2_2") (pintype "passive"))
      (node (ref "S234") (pin "2") (pinfunction "2_2") (pintype "passive"))
      (node (ref "S248") (pin "2") (pinfunction "2_2") (pintype "passive"))
    )
    (net (code "7") (name "/col7") (class "Default")
      (node (ref "S207") (pin "2") (pinfunction "2_2") (pintype "passive"))
      (node (ref "S221") (pin "2") (pinfunction "2_2") (pintype "passive"))
      (node (ref "S235") (pin "2") (pinfunction "2_2") (pintype "passive"))
      (node (ref "S249") (pin "2") (pinfunction "2_2") (pintype "passive"))
      (node (ref "S262") (pin "1") (pinfunction "1_1") (pintype "passive"))
      (node (ref "S262_1") (pin "1") (pinfunction "1_1") (pintype "passive"))
      (node (ref "S262_2") (pin "1") (pinfunction "1_1") (pintype "passive"))
    )
    (net (code "8") (name "/col8") (class "Default")
      (node (ref "S208") (pin "2") (pinfunction "2_2") (pintype "passive"))
      (node (ref "S222") (pin "2") (pinfunction "2_2") (pintype "passive"))
      (node (ref "S236") (pin "2") (pinfunction "2_2") (pintype "passive"))
      (node (ref "S250") (pin "2") (pinfunction "2_2") (pintype "passive"))
    )
    (net (code "9") (name "/col9") (class "Default")
      (node (ref "S209") (pin "2") (pinfunction "2_2") (pintype "passive"))
      (node (ref "S223") (pin "2") (pinfunction "2_2") (pintype "passive"))
      (node (ref "S237") (pin "2") (pinfunction "2_2") (pintype "passive"))
      (node (ref "S251") (pin "2") (pinfunction "2_2") (pintype "passive"))
      (node (ref "S263") (pin "1") (pinfunction "1_1") (pintype "passive"))
      (node (ref "S263_1") (pin "1") (pinfunction "1_1") (pintype "passive"))
    )
    (net (code "10") (name "/col10") (class "Default")
      (node (ref "S210") (pin "2") (pinfunction "2_2") (pintype "passive"))
      (node (ref "S224") (pin "2") (pinfunction "2_2") (pintype "passive"))
      (node (ref "S238") (pin "2") (pinfunction "2_2") (pintype "passive"))
      (node (ref "S252") (pin "2") (pinfunction "2_2") (pintype "passive"))
      (node (ref "S264") (pin "2") (pinfunction "2_2") (pintype "passive"))
    )
    (net (code "11") (name "/col11") (class "Default")
      (node (ref "S211") (pin "2") (pinfunction "2_2") (pintype "passive"))
      (node (ref "S225") (pin "2") (pinfunction "2_2") (pintype "passive"))
      (node (ref "S239") (pin "2") (pinfunction "2_2") (pintype "passive"))
      (node (ref "S253") (pin "2") (pinfunction "2_2") (pintype "passive"))
      (node (ref "S265") (pin "1") (pinfunction "1_1") (pintype "passive"))
      (node (ref "S265_1") (pin "1") (pinfunction "1_1") (pintype "passive"))
    )
    (net (code "12") (name "/col12") (class "Default")
      (node (ref "S212") (pin "2") (pinfunction "2_2") (pintype "passive"))
      (node (ref "S226") (pin "2") (pinfunction "2_2") (pintype "passive"))
      (node (ref "S240") (pin "2") (pinfunction "2_2") (pintype "passive"))
      (node (ref "S241") (pin "1") (pinfunction "1_1") (pintype "passive"))
      (node (ref "S241_1") (pin "1") (pinfunction "1_1") (pintype "passive"))
      (node (ref "S254") (pin "2") (pinfunction "2_2") (pintype "passive"))
    )
    (net (code "13") (name "/col13") (class "Default")
      (node (ref "S213") (pin "2") (pinfunction "2_2") (pintype "passive"))
      (node (ref "S227") (pin "2") (pinfunction "2_2") (pintype "passive"))
      (node (ref "S256") (pin "2") (pinfunction "2_2") (pintype "passive"))
      (node (ref "S256_1") (pin "2") (pinfunction "2_2") (pintype "passive"))
      (node (ref "S256_2") (pin "2") (pinfunction "2_2") (pintype "passive"))
      (node (ref "S266") (pin "2") (pinfunction "2_2") (pintype "passive"))
      (node (ref "S266_1") (pin "2") (pinfunction "2_2") (pintype "passive"))
      (node (ref "S271") (pin "2") (pinfunction "2_2") (pintype "passive"))
    )
    (net (code "14") (name "/col14") (class "Default")
      (node (ref "S214") (pin "2") (pinfunction "2_2") (pintype "passive"))
      (node (ref "S228") (pin "2") (pinfunction "2_2") (pintype "passive"))
      (node (ref "S228_1") (pin "2") (pinfunction "2_2") (pintype "passive"))
      (node (ref "S242") (pin "2") (pinfunction "2_2") (pintype "passive"))
      (node (ref "S242_1") (pin "2") (pinfunction "2_2") (pintype "passive"))
      (node (ref "S242_2") (pin "2") (pinfunction "2_2") (pintype "passive"))
      (node (ref "S259") (pin "1") (pinfunction "1_1") (pintype "passive"))
      (node (ref "S259_1") (pin "2") (pinfunction "2_2") (pintype "passive"))
      (node (ref "S269") (pin "2") (pinfunction "2_2") (pintype "passive"))
    )
    (net (code "15") (name "/row1") (class "Default")
      (node (ref "D201") (pin "2") (pinfunction "K_2") (pintype "passive"))
      (node (ref "D202") (pin "2") (pinfunction "K_2") (pintype "passive"))
      (node (ref "D203") (pin "2") (pinfunction "K_2") (pintype "passive"))
      (node (ref "D204") (pin "2") (pinfunction "K_2") (pintype "passive"))
      (node (ref "D205") (pin "2") (pinfunction "K_2") (pintype "passive"))
      (node (ref "D206") (pin "2") (pinfunction "K_2") (pintype "passive"))
      (node (ref "D207") (pin "2") (pinfunction "K_2") (pintype "passive"))
      (node (ref "D208") (pin "2") (pinfunction "K_2") (pintype "passive"))
      (node (ref "D209") (pin "2") (pinfunction "K_2") (pintype "passive"))
      (node (ref "D210") (pin "2") (pinfunction "K_2") (pintype "passive"))
      (node (ref "D211") (pin "2") (pinfunction "K_2") (pintype "passive"))
      (node (ref "D212") (pin "2") (pinfunction "K_2") (pintype "passive"))
      (node (ref "D213") (pin "2") (pinfunction "K_2") (pintype "passive"))
      (node (ref "D214") (pin "2") (pinfunction "K_2") (pintype "passive"))
    )
    (net (code "16") (name "/row2") (class "Default")
      (node (ref "D215") (pin "2") (pinfunction "K_2") (pintype "passive"))
      (node (ref "D216") (pin "2") (pinfunction "K_2") (pintype "passive"))
      (node (ref "D217") (pin "2") (pinfunction "K_2") (pintype "passive"))
      (node (ref "D218") (pin "2") (pinfunction "K_2") (pintype "passive"))
      (node (ref "D219") (pin "2") (pinfunction "K_2") (pintype "passive"))
      (node (ref "D220") (pin "2") (pinfunction "K_2") (pintype "passive"))
      (node (ref "D221") (pin "2") (pinfunction "K_2") (pintype "passive"))
      (node (ref "D222") (pin "2") (pinfunction "K_2") (pintype "passive"))
      (node (ref "D223") (pin "2") (pinfunction "K_2") (pintype "passive"))
      (node (ref "D224") (pin "2") (pinfunction "K_2") (pintype "passive"))
      (node (ref "D225") (pin "2") (pinfunction "K_2") (pintype "passive"))
      (node (ref "D226") (pin "2") (pinfunction "K_2") (pintype "passive"))
      (node (ref "D227") (pin "2") (pinfunction "K_2") (pintype "passive"))
      (node (ref "D228") (pin "2") (pinfunction "K_2") (pintype "passive"))
    )
    (net (code "17") (name "/row3") (class "Default")
      (node (ref "D229") (pin "2") (pinfunction "K_2") (pintype "passive"))
      (node (ref "D230") (pin "2") (pinfunction "K_2") (pintype "passive"))
      (node (ref "D231") (pin "2") (pinfunction "K_2") (pintype "passive"))
      (node (ref "D232") (pin "2") (pinfunction "K_2") (pintype "passive"))
      (node (ref "D233") (pin "2") (pinfunction "K_2") (pintype "passive"))
      (node (ref "D234") (pin "2") (pinfunction "K_2") (pintype "passive"))
      (node (ref "D235") (pin "2") (pinfunction "K_2") (pintype "passive"))
      (node (ref "D236") (pin "2") (pinfunction "K_2") (pintype "passive"))
      (node (ref "D237") (pin "2") (pinfunction "K_2") (pintype "passive"))
      (node (ref "D238") (pin "2") (pinfunction "K_2") (pintype "passive"))
      (node (ref "D239") (pin "2") (pinfunction "K_2") (pintype "passive"))
      (node (ref "D240") (pin "2") (pinfunction "K_2") (pintype "passive"))
      (node (ref "D259") (pin "2") (pinfunction "K_2") (pintype "passive"))
      (node (ref "D271") (pin "2") (pinfunction "K_2") (pintype "passive"))
    )
    (net (code "18") (name "/row4") (class "Default")
      (node (ref "D242") (pin "2") (pinfunction "K_2") (pintype "passive"))
      (node (ref "D243") (pin "2") (pinfunction "K_2") (pintype "passive"))
      (node (ref "D244") (pin "2") (pinfunction "K_2") (pintype "passive"))
      (node (ref "D245") (pin "2") (pinfunction "K_2") (pintype "passive"))
      (node (ref "D246") (pin "2") (pinfunction "K_2") (pintype "passive"))
      (node (ref "D247") (pin "2") (pinfunction "K_2") (pintype "passive"))
      (node (ref "D248") (pin "2") (pinfunction "K_2") (pintype "passive"))
      (node (ref "D249") (pin "2") (pinfunction "K_2") (pintype "passive"))
      (node (ref "D250") (pin "2") (pinfunction "K_2") (pintype "passive"))
      (node (ref "D251") (pin "2") (pinfunction "K_2") (pintype "passive"))
      (node (ref "D252") (pin "2") (pinfunction "K_2") (pintype "passive"))
      (node (ref "D253") (pin "2") (pinfunction "K_2") (pintype "passive"))
      (node (ref "D254") (pin "2") (pinfunction "K_2") (pintype "passive"))
      (node (ref "D255") (pin "2") (pinfunction "K_2") (pintype "passive"))
    )
    (net (code "19") (name "/row5") (class "Default")
      (node (ref "D241") (pin "2") (pinfunction "K_2") (pintype "passive"))
      (node (ref "D256") (pin "2") (pinfunction "K_2") (pintype "passive"))
      (node (ref "D257") (pin "2") (pinfunction "K_2") (pintype "passive"))
      (node (ref "D258") (pin "2") (pinfunction "K_2") (pintype "passive"))
      (node (ref "D260") (pin "2") (pinfunction "K_2") (pintype "passive"))
      (node (ref "D261") (pin "2") (pinfunction "K_2") (pintype "passive"))
      (node (ref "D262") (pin "2") (pinfunction "K_2") (pintype "passive"))
      (node (ref "D263") (pin "2") (pinfunction "K_2") (pintype "passive"))
      (node (ref "D264") (pin "2") (pinfunction "K_2") (pintype "passive"))
      (node (ref "D265") (pin "2") (pinfunction "K_2") (pintype "passive"))
      (node (ref "D266") (pin "2") (pinfunction "K_2") (pintype "passive"))
    )
    (net (code "20") (name "Net-(D201-A)") (class "Default")
      (node (ref "D201") (pin "1") (pinfunction "A_1") (pintype "passive"))
      (node (ref "S201") (pin "1") (pinfunction "1_1") (pintype "passive"))
    )
    (net (code "21") (name "Net-(D202-A)") (class "Default")
      (node (ref "D202") (pin "1") (pinfunction "A_1") (pintype "passive"))
      (node (ref "S202") (pin "1") (pinfunction "1_1") (pintype "passive"))
    )
    (net (code "22") (name "Net-(D203-A)") (class "Default")
      (node (ref "D203") (pin "1") (pinfunction "A_1") (pintype "passive"))
      (node (ref "S203") (pin "1") (pinfunction "1_1") (pintype "passive"))
    )
    (net (code "23") (name "Net-(D204-A)") (class "Default")
      (node (ref "D204") (pin "1") (pinfunction "A_1") (pintype "passive"))
      (node (ref "S204") (pin "1") (pinfunction "1_1") (pintype "passive"))
    )
    (net (code "24") (name "Net-(D205-A)") (class "Default")
      (node (ref "D205") (pin "1") (pinfunction "A_1") (pintype "passive"))
      (node (ref "S205") (pin "1") (pinfunction "1_1") (pintype "passive"))
    )
    (net (code "25") (name "Net-(D206-A)") (class "Default")
      (node (ref "D206") (pin "1") (pinfunction "A_1") (pintype "passive"))
      (node (ref "S206") (pin "1") (pinfunction "1_1") (pintype "passive"))
    )
    (net (code "26") (name "Net-(D207-A)") (class "Default")
      (node (ref "D207") (pin "1") (pinfunction "A_1") (pintype "passive"))
      (node (ref "S207") (pin "1") (pinfunction "1_1") (pintype "passive"))
    )
    (net (code "27") (name "Net-(D208-A)") (class "Default")
      (node (ref "D208") (pin "1") (pinfunction "A_1") (pintype "passive"))
      (node (ref "S208") (pin "1") (pinfunction "1_1") (pintype "passive"))
    )
    (net (code "28") (name "Net-(D209-A)") (class "Default")
      (node (ref "D209") (pin "1") (pinfunction "A_1") (pintype "passive"))
      (node (ref "S209") (pin "1") (pinfunction "1_1") (pintype "passive"))
    )
    (net (code "29") (name "Net-(D210-A)") (class "Default")
      (node (ref "D210") (pin "1") (pinfunction "A_1") (pintype "passive"))
      (node (ref "S210") (pin "1") (pinfunction "1_1") (pintype "passive"))
    )
    (net (code "30") (name "Net-(D211-A)") (class "Default")
      (node (ref "D211") (pin "1") (pinfunction "A_1") (pintype "passive"))
      (node (ref "S211") (pin "1") (pinfunction "1_1") (pintype "passive"))
    )
    (net (code "31") (name "Net-(D212-A)") (class "Default")
      (node (ref "D212") (pin "1") (pinfunction "A_1") (pintype "passive"))
      (node (ref "S212") (pin "1") (pinfunction "1_1") (pintype "passive"))
    )
    (net (code "32") (name "Net-(D213-A)") (class "Default")
      (node (ref "D213") (pin "1") (pinfunction "A_1") (pintype "passive"))
      (node (ref "S213") (pin "1") (pinfunction "1_1") (pintype "passive"))
    )
    (net (code "33") (name "Net-(D214-A)") (class "Default")
      (node (ref "D214") (pin "1") (pinfunction "A_1") (pintype "passive"))
      (node (ref "S214") (pin "1") (pinfunction "1_1") (pintype "passive"))
    )
    (net (code "34") (name "Net-(D215-A)") (class "Default")
      (node (ref "D215") (pin "1") (pinfunction "A_1") (pintype "passive"))
      (node (ref "S215") (pin "1") (pinfunction "1_1") (pintype "passive"))
      (node (ref "S215_1") (pin "1") (pinfunction "1_1") (pintype "passive"))
    )
    (net (code "35") (name "Net-(D216-A)") (class "Default")
      (node (ref "D216") (pin "1") (pinfunction "A_1") (pintype "passive"))
      (node (ref "S216") (pin "1") (pinfunction "1_1") (pintype "passive"))
    )
    (net (code "36") (name "Net-(D217-A)") (class "Default")
      (node (ref "D217") (pin "1") (pinfunction "A_1") (pintype "passive"))
      (node (ref "S217") (pin "1") (pinfunction "1_1") (pintype "passive"))
    )
    (net (code "37") (name "Net-(D218-A)") (class "Default")
      (node (ref "D218") (pin "1") (pinfunction "A_1") (pintype "passive"))
      (node (ref "S218") (pin "1") (pinfunction "1_1") (pintype "passive"))
    )
    (net (code "38") (name "Net-(D219-A)") (class "Default")
      (node (ref "D219") (pin "1") (pinfunction "A_1") (pintype "passive"))
      (node (ref "S219") (pin "1") (pinfunction "1_1") (pintype "passive"))
    )
    (net (code "39") (name "Net-(D220-A)") (class "Default")
      (node (ref "D220") (pin "1") (pinfunction "A_1") (pintype "passive"))
      (node (ref "S220") (pin "1") (pinfunction "1_1") (pintype "passive"))
    )
    (net (code "40") (name "Net-(D221-A)") (class "Default")
      (node (ref "D221") (pin "1") (pinfunction "A_1") (pintype "passive"))
      (node (ref "S221") (pin "1") (pinfunction "1_1") (pintype "passive"))
    )
    (net (code "41") (name "Net-(D222-A)") (class "Default")
      (node (ref "D222") (pin "1") (pinfunction "A_1") (pintype "passive"))
      (node (ref "S222") (pin "1") (pinfunction "1_1") (pintype "passive"))
    )
    (net (code "42") (name "Net-(D223-A)") (class "Default")
      (node (ref "D223") (pin "1") (pinfunction "A_1") (pintype "passive"))
      (node (ref "S223") (pin "1") (pinfunction "1_1") (pintype "passive"))
    )
    (net (code "43") (name "Net-(D224-A)") (class "Default")
      (node (ref "D224") (pin "1") (pinfunction "A_1") (pintype "passive"))
      (node (ref "S224") (pin "1") (pinfunction "1_1") (pintype "passive"))
    )
    (net (code "44") (name "Net-(D225-A)") (class "Default")
      (node (ref "D225") (pin "1") (pinfunction "A_1") (pintype "passive"))
      (node (ref "S225") (pin "1") (pinfunction "1_1") (pintype "passive"))
    )
    (net (code "45") (name "Net-(D226-A)") (class "Default")
      (node (ref "D226") (pin "1") (pinfunction "A_1") (pintype "passive"))
      (node (ref "S226") (pin "1") (pinfunction "1_1") (pintype "passive"))
    )
    (net (code "46") (name "Net-(D227-A)") (class "Default")
      (node (ref "D227") (pin "1") (pinfunction "A_1") (pintype "passive"))
      (node (ref "S227") (pin "1") (pinfunction "1_1") (pintype "passive"))
    )
    (net (code "47") (name "Net-(D228-A)") (class "Default")
      (node (ref "D228") (pin "1") (pinfunction "A_1") (pintype "passive"))
      (node (ref "S228") (pin "1") (pinfunction "1_1") (pintype "passive"))
      (node (ref "S228_1") (pin "1") (pinfunction "1_1") (pintype "passive"))
    )
    (net (code "48") (name "Net-(D229-A)") (class "Default")
      (node (ref "D229") (pin "1") (pinfunction "A_1") (pintype "passive"))
      (node (ref "S229") (pin "2") (pinfunction "2_2") (pintype "passive"))
    )
    (net (code "49") (name "Net-(D230-A)") (class "Default")
      (node (ref "D230") (pin "1") (pinfunction "A_1") (pintype "passive"))
      (node (ref "S230") (pin "1") (pinfunction "1_1") (pintype "passive"))
    )
    (net (code "50") (name "Net-(D231-A)") (class "Default")
      (node (ref "D231") (pin "1") (pinfunction "A_1") (pintype "passive"))
      (node (ref "S231") (pin "1") (pinfunction "1_1") (pintype "passive"))
    )
    (net (code "51") (name "Net-(D232-A)") (class "Default")
      (node (ref "D232") (pin "1") (pinfunction "A_1") (pintype "passive"))
      (node (ref "S232") (pin "1") (pinfunction "1_1") (pintype "passive"))
    )
    (net (code "52") (name "Net-(D233-A)") (class "Default")
      (node (ref "D233") (pin "1") (pinfunction "A_1") (pintype "passive"))
      (node (ref "S233") (pin "1") (pinfunction "1_1") (pintype "passive"))
    )
    (net (code "53") (name "Net-(D234-A)") (class "Default")
      (node (ref "D234") (pin "1") (pinfunction "A_1") (pintype "passive"))
      (node (ref "S234") (pin "1") (pinfunction "1_1") (pintype "passive"))
    )
    (net (code "54") (name "Net-(D235-A)") (class "Default")
      (node (ref "D235") (pin "1") (pinfunction "A_1") (pintype "passive"))
      (node (ref "S235") (pin "1") (pinfunction "1_1") (pintype "passive"))
    )
    (net (code "55") (name "Net-(D236-A)") (class "Default")
      (node (ref "D236") (pin "1") (pinfunction "A_1") (pintype "passive"))
      (node (ref "S236") (pin "1") (pinfunction "1_1") (pintype "passive"))
    )
    (net (code "56") (name "Net-(D237-A)") (class "Default")
      (node (ref "D237") (pin "1") (pinfunction "A_1") (pintype "passive"))
      (node (ref "S237") (pin "1") (pinfunction "1_1") (pintype "passive"))
    )
    (net (code "57") (name "Net-(D238-A)") (class "Default")
      (node (ref "D238") (pin "1") (pinfunction "A_1") (pintype "passive"))
      (node (ref "S238") (pin "1") (pinfunction "1_1") (pintype "passive"))
    )
    (net (code "58") (name "Net-(D239-A)") (class "Default")
      (node (ref "D239") (pin "1") (pinfunction "A_1") (pintype "passive"))
      (node (ref "S239") (pin "1") (pinfunction "1_1") (pintype "passive"))
    )
    (net (code "59") (name "Net-(D240-A)") (class "Default")
      (node (ref "D240") (pin "1") (pinfunction "A_1") (pintype "passive"))
      (node (ref "S240") (pin "1") (pinfunction "1_1") (pintype "passive"))
    )
    (net (code "60") (name "Net-(D241-A)") (class "Default")
      (node (ref "D241") (pin "1") (pinfunction "A_1") (pintype "passive"))
      (node (ref "S241") (pin "2") (pinfunction "2_2") (pintype "passive"))
      (node (ref "S241_1") (pin "2") (pinfunction "2_2") (pintype "passive"))
    )
    (net (code "61") (name "Net-(D242-A)") (class "Default")
      (node (ref "D242") (pin "1") (pinfunction "A_1") (pintype "passive"))
      (node (ref "S242") (pin "1") (pinfunction "1_1") (pintype "passive"))
      (node (ref "S242_1") (pin "1") (pinfunction "1_1") (pintype "passive"))
      (node (ref "S242_2") (pin "1") (pinfunction "1_1") (pintype "passive"))
    )
    (net (code "62") (name "Net-(D243-A)") (class "Default")
      (node (ref "D243") (pin "1") (pinfunction "A_1") (pintype "passive"))
      (node (ref "S243") (pin "1") (pinfunction "1_1") (pintype "passive"))
      (node (ref "S243_1") (pin "1") (pinfunction "1_1") (pintype "passive"))
      (node (ref "S243_2") (pin "1") (pinfunction "1_1") (pintype "passive"))
      (node (ref "S243_3") (pin "1") (pinfunction "1_1") (pintype "passive"))
    )
    (net (code "63") (name "Net-(D244-A)") (class "Default")
      (node (ref "D244") (pin "1") (pinfunction "A_1") (pintype "passive"))
      (node (ref "S244") (pin "2") (pinfunction "2_2") (pintype "passive"))
    )
    (net (code "64") (name "Net-(D245-A)") (class "Default")
      (node (ref "D245") (pin "1") (pinfunction "A_1") (pintype "passive"))
      (node (ref "S245") (pin "1") (pinfunction "1_1") (pintype "passive"))
    )
    (net (code "65") (name "Net-(D246-A)") (class "Default")
      (node (ref "D246") (pin "1") (pinfunction "A_1") (pintype "passive"))
      (node (ref "S246") (pin "1") (pinfunction "1_1") (pintype "passive"))
    )
    (net (code "66") (name "Net-(D247-A)") (class "Default")
      (node (ref "D247") (pin "1") (pinfunction "A_1") (pintype "passive"))
      (node (ref "S247") (pin "1") (pinfunction "1_1") (pintype "passive"))
    )
    (net (code "67") (name "Net-(D248-A)") (class "Default")
      (node (ref "D248") (pin "1") (pinfunction "A_1") (pintype "passive"))
      (node (ref "S248") (pin "1") (pinfunction "1_1") (pintype "passive"))
    )
    (net (code "68") (name "Net-(D249-A)") (class "Default")
      (node (ref "D249") (pin "1") (pinfunction "A_1") (pintype "passive"))
      (node (ref "S249") (pin "1") (pinfunction "1_1") (pintype "passive"))
    )
    (net (code "69") (name "Net-(D250-A)") (class "Default")
      (node (ref "D250") (pin "1") (pinfunction "A_1") (pintype "passive"))
      (node (ref "S250") (pin "1") (pinfunction "1_1") (pintype "passive"))
    )
    (net (code "70") (name "Net-(D251-A)") (class "Default")
      (node (ref "D251") (pin "1") (pinfunction "A_1") (pintype "passive"))
      (node (ref "S251") (pin "1") (pinfunction "1_1") (pintype "passive"))
    )
    (net (code "71") (name "Net-(D252-A)") (class "Default")
      (node (ref "D252") (pin "1") (pinfunction "A_1") (pintype "passive"))
      (node (ref "S252") (pin "1") (pinfunction "1_1") (pintype "passive"))
    )
    (net (code "72") (name "Net-(D253-A)") (class "Default")
      (node (ref "D253") (pin "1") (pinfunction "A_1") (pintype "passive"))
      (node (ref "S253") (pin "1") (pinfunction "1_1") (pintype "passive"))
    )
    (net (code "73") (name "Net-(D254-A)") (class "Default")
      (node (ref "D254") (pin "1") (pinfunction "A_1") (pintype "passive"))
      (node (ref "S254") (pin "1") (pinfunction "1_1") (pintype "passive"))
    )
    (net (code "74") (name "Net-(D255-A)") (class "Default")
      (node (ref "D255") (pin "1") (pinfunction "A_1") (pintype "passive"))
      (node (ref "S256") (pin "1") (pinfunction "1_1") (pintype "passive"))
      (node (ref "S256_1") (pin "1") (pinfunction "1_1") (pintype "passive"))
      (node (ref "S256_2") (pin "1") (pinfunction "1_1") (pintype "passive"))
    )
    (net (code "75") (name "Net-(D256-A)") (class "Default")
      (node (ref "D256") (pin "1") (pinfunction "A_1") (pintype "passive"))
      (node (ref "S269") (pin "1") (pinfunction "1_1") (pintype "passive"))
    )
    (net (code "76") (name "Net-(D257-A)") (class "Default")
      (node (ref "D257") (pin "1") (pinfunction "A_1") (pintype "passive"))
      (node (ref "S257") (pin "2") (pinfunction "2_2") (pintype "passive"))
      (node (ref "S257_1") (pin "2") (pinfunction "2_2") (pintype "passive"))
    )
    (net (code "77") (name "Net-(D258-A)") (class "Default")
      (node (ref "D258") (pin "1") (pinfunction "A_1") (pintype "passive"))
      (node (ref "S258") (pin "1") (pinfunction "1_1") (pintype "passive"))
      (node (ref "S258_1") (pin "2") (pinfunction "2_2") (pintype "passive"))
    )
    (net (code "78") (name "Net-(D259-A)") (class "Default")
      (node (ref "D259") (pin "1") (pinfunction "A_1") (pintype "passive"))
      (node (ref "S259") (pin "1") (pinfunction "1_1") (pintype "passive"))
      (node (ref "S259_1") (pin "1") (pinfunction "1_1") (pintype "passive"))
    )
    (net (code "79") (name "Net-(D260-A)") (class "Default")
      (node (ref "D260") (pin "1") (pinfunction "A_1") (pintype "passive"))
      (node (ref "S260") (pin "1") (pinfunction "1_1") (pintype "passive"))
      (node (ref "S260_1") (pin "2") (pinfunction "2_2") (pintype "passive"))
    )
    (net (code "80") (name "Net-(D261-A)") (class "Default")
      (node (ref "D261") (pin "1") (pinfunction "A_1") (pintype "passive"))
      (node (ref "S261") (pin "1") (pinfunction "1_1") (pintype "passive"))
      (node (ref "S261_1") (pin "1") (pinfunction "1_1") (pintype "passive"))
    )
    (net (code "81") (name "Net-(D262-A)") (class "Default")
      (node (ref "D262") (pin "1") (pinfunction "A_1") (pintype "passive"))
      (node (ref "S262") (pin "2") (pinfunction "2_2") (pintype "passive"))
      (node (ref "S262_1") (pin "2") (pinfunction "2_2") (pintype "passive"))
      (node (ref "S262_2") (pin "2") (pinfunction "2_2") (pintype "passive"))
    )
    (net (code "82") (name "Net-(D263-A)") (class "Default")
      (node (ref "D263") (pin "1") (pinfunction "A_1") (pintype "passive"))
      (node (ref "S263") (pin "2") (pinfunction "2_2") (pintype "passive"))
      (node (ref "S263_1") (pin "2") (pinfunction "2_2") (pintype "passive"))
    )
    (net (code "83") (name "Net-(D264-A)") (class "Default")
      (node (ref "D264") (pin "1") (pinfunction "A_1") (pintype "passive"))
      (node (ref "S264") (pin "1") (pinfunction "1_1") (pintype "passive"))
    )
    (net (code "84") (name "Net-(D265-A)") (class "Default")
      (node (ref "D265") (pin "1") (pinfunction "A_1") (pintype "passive"))
      (node (ref "S265") (pin "2") (pinfunction "2_2") (pintype "passive"))
      (node (ref "S265_1") (pin "2") (pinfunction "2_2") (pintype "passive"))
    )
    (net (code "85") (name "Net-(D266-A)") (class "Default")
      (node (ref "D266") (pin "1") (pinfunction "A_1") (pintype "passive"))
      (node (ref "S266") (pin "1") (pinfunction "1_1") (pintype "passive"))
      (node (ref "S266_1") (pin "1") (pinfunction "1_1") (pintype "passive"))
    )
    (net (code "86") (name "Net-(D271-A)") (class "Default")
      (node (ref "D271") (pin "1") (pinfunction "A_1") (pintype "passive"))
      (node (ref "S271") (pin "1") (pinfunction "1_1") (pintype "passive"))
    )
  )
)
